# Conectores_Finales.net
KiCad netlist of a schematic drawn in Altium Designer
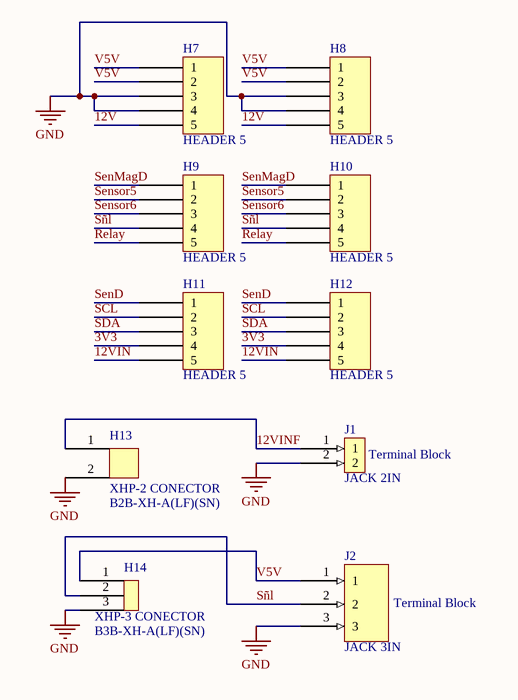
[diagram p0: Conectores Finales.SchDoc]

(export (version "E")
  (design (tool "Eeschema 10.0.6"))
  (components
    (comp (ref "H7") (value "HEADER 5") (footprint "HEADER5") (libsource (lib "seguintII") (part "HEADER 5")))
    (comp (ref "H8") (value "HEADER 5") (footprint "HEADER5") (libsource (lib "seguintII") (part "HEADER 5")))
    (comp (ref "H9") (value "HEADER 5") (footprint "HEADER5") (libsource (lib "seguintII") (part "HEADER 5")))
    (comp (ref "H10")
      (value "HEADER 5")
      (footprint "HEADER5")
      (libsource (lib "seguintII") (part "HEADER 5"))
    )
    (comp (ref "H11")
      (value "HEADER 5")
      (footprint "HEADER5")
      (libsource (lib "seguintII") (part "HEADER 5"))
    )
    (comp (ref "H12")
      (value "HEADER 5")
      (footprint "HEADER5")
      (libsource (lib "seguintII") (part "HEADER 5"))
    )
    (comp (ref "H13")
      (value "XHP-2 CONECTOR")
      (footprint "CONECTOR 2 PINES")
      (description "CONECTOR JST-XH 2 PINES")
      (fields (field (name "SUPPLIER NUMBER PART") "B2B-XH-A(LF)(SN)"))
      (libsource (lib "Practica 1") (part "B2B-XH-A(LF)(SN)"))
    )
    (comp (ref "H14")
      (value "XHP-3 CONECTOR")
      (footprint "CONECTOR XHP-3")
      (description "CONECTOR JST-XH 3 PINES")
      (fields (field (name "SUPPLIER NUMBER PART") "B3B-XH-A(LF)(SN)"))
      (libsource (lib "Practica 1") (part "B3B-XH-A(LF)(SN)"))
    )
    (comp (ref "J1")
      (value "JACK 2IN")
      (footprint "Terminal Blocks 2in")
      (description "Pluggable Terminal Blocks WR-TBL Mod312 5.08mm 2Pin Opn Hztl PCBHdr")
      (fields
        (field (name "MANUFACTURER") "Wurth Electronics")
        (field (name "MANUFACTURER PART NUMBER") "691312510002")
      )
      (libsource (lib "seguintII") (part "JACK 2IN"))
    )
    (comp (ref "J2")
      (value "JACK 3IN")
      (footprint "Terminal Blocks 3in")
      (description "Pluggable Terminal Blocks WR-TBL Mod312 5.08mm 3Pin Opn Hztl PCBHdr")
      (fields
        (field (name "MANUFACTURER") "Wurth Electronics")
        (field (name "MANUFACTURER PART NUMBER") "691312510003")
      )
      (libsource (lib "seguintII") (part "JACK 3IN"))
    )
  )
  (nets
    (net (code "1") (name "/3V3") (class "Default")
      (node (ref "H11") (pin "4") (pinfunction "4_4") (pintype "passive"))
      (node (ref "H12") (pin "4") (pinfunction "4_4") (pintype "passive"))
    )
    (net (code "2") (name "/12V") (class "Default")
      (node (ref "H7") (pin "5") (pinfunction "5_5") (pintype "passive"))
      (node (ref "H8") (pin "5") (pinfunction "5_5") (pintype "passive"))
    )
    (net (code "3") (name "/12VIN") (class "Default")
      (node (ref "H11") (pin "5") (pinfunction "5_5") (pintype "passive"))
      (node (ref "H12") (pin "5") (pinfunction "5_5") (pintype "passive"))
    )
    (net (code "4") (name "/12VINF") (class "Default")
      (node (ref "H13") (pin "1") (pinfunction "1_1") (pintype "passive"))
      (node (ref "J1") (pin "1") (pinfunction "1_1") (pintype "input"))
    )
    (net (code "5") (name "/Relay") (class "Default")
      (node (ref "H10") (pin "5") (pinfunction "5_5") (pintype "passive"))
      (node (ref "H9") (pin "5") (pinfunction "5_5") (pintype "passive"))
    )
    (net (code "6") (name "/SCL") (class "Default")
      (node (ref "H11") (pin "2") (pinfunction "2_2") (pintype "passive"))
      (node (ref "H12") (pin "2") (pinfunction "2_2") (pintype "passive"))
    )
    (net (code "7") (name "/SDA") (class "Default")
      (node (ref "H11") (pin "3") (pinfunction "3_3") (pintype "passive"))
      (node (ref "H12") (pin "3") (pinfunction "3_3") (pintype "passive"))
    )
    (net (code "8") (name "/SenD") (class "Default")
      (node (ref "H11") (pin "1") (pinfunction "1_1") (pintype "passive"))
      (node (ref "H12") (pin "1") (pinfunction "1_1") (pintype "passive"))
    )
    (net (code "9") (name "/SenMagD") (class "Default")
      (node (ref "H10") (pin "1") (pinfunction "1_1") (pintype "passive"))
      (node (ref "H9") (pin "1") (pinfunction "1_1") (pintype "passive"))
    )
    (net (code "10") (name "/Sensor5") (class "Default")
      (node (ref "H10") (pin "2") (pinfunction "2_2") (pintype "passive"))
      (node (ref "H9") (pin "2") (pinfunction "2_2") (pintype "passive"))
    )
    (net (code "11") (name "/Sensor6") (class "Default")
      (node (ref "H10") (pin "3") (pinfunction "3_3") (pintype "passive"))
      (node (ref "H9") (pin "3") (pinfunction "3_3") (pintype "passive"))
    )
    (net (code "12") (name "/Sñl") (class "Default")
      (node (ref "H10") (pin "4") (pinfunction "4_4") (pintype "passive"))
      (node (ref "H14") (pin "2") (pinfunction "2_2") (pintype "passive"))
      (node (ref "H9") (pin "4") (pinfunction "4_4") (pintype "passive"))
      (node (ref "J2") (pin "2") (pinfunction "2_2") (pintype "input"))
    )
    (net (code "13") (name "/V5V") (class "Default")
      (node (ref "H14") (pin "1") (pinfunction "1_1") (pintype "passive"))
      (node (ref "H7") (pin "1") (pinfunction "1_1") (pintype "passive"))
      (node (ref "H7") (pin "2") (pinfunction "2_2") (pintype "passive"))
      (node (ref "H8") (pin "1") (pinfunction "1_1") (pintype "passive"))
      (node (ref "H8") (pin "2") (pinfunction "2_2") (pintype "passive"))
      (node (ref "J2") (pin "1") (pinfunction "1_1") (pintype "input"))
    )
    (net (code "14") (name "GND") (class "Default")
      (node (ref "H13") (pin "2") (pinfunction "2_2") (pintype "passive"))
      (node (ref "H14") (pin "3") (pinfunction "3_3") (pintype "passive"))
      (node (ref "H7") (pin "3") (pinfunction "3_3") (pintype "passive"))
      (node (ref "H7") (pin "4") (pinfunction "4_4") (pintype "passive"))
      (node (ref "H8") (pin "3") (pinfunction "3_3") (pintype "passive"))
      (node (ref "H8") (pin "4") (pinfunction "4_4") (pintype "passive"))
      (node (ref "J1") (pin "2") (pinfunction "2_2") (pintype "input"))
      (node (ref "J2") (pin "3") (pinfunction "3_3") (pintype "input"))
    )
  )
)
